# pic18f13k50_3.net
KiCad netlist of a schematic drawn in EAGLE
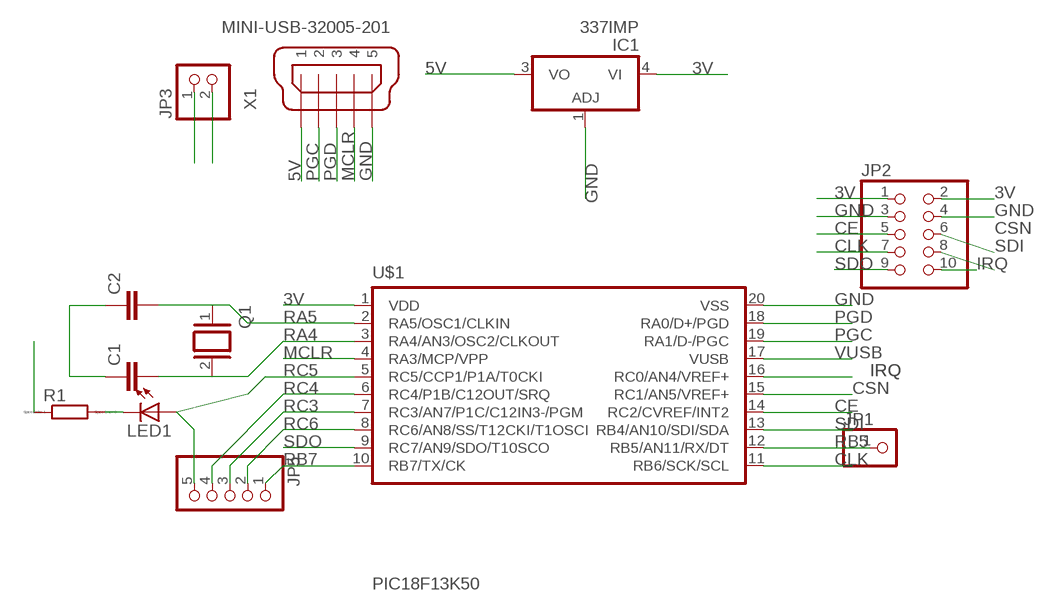
[diagram p0: schematic, sheet 1]

(export (version "E")
  (design (tool "Eeschema 10.0.6"))
  (components
    (comp (ref "C1")
      (value "C-EUC0805")
      (footprint "eagle-import:C0805")
      (libsource (lib "eagle-import") (part "C-EUC0805"))
    )
    (comp (ref "C2")
      (value "C-EUC0805")
      (footprint "eagle-import:C0805")
      (libsource (lib "eagle-import") (part "C-EUC0805"))
    )
    (comp (ref "IC1")
      (value "337IMP")
      (footprint "eagle-import:SOT223")
      (libsource (lib "eagle-import") (part "337IMP"))
    )
    (comp (ref "JP1")
      (value "PINHD-1X1")
      (footprint "eagle-import:1X01")
      (libsource (lib "eagle-import") (part "PINHD-1X1"))
    )
    (comp (ref "JP2")
      (value "PINHD-2X5")
      (footprint "eagle-import:2X05")
      (libsource (lib "eagle-import") (part "PINHD-2X5"))
    )
    (comp (ref "JP3")
      (value "PINHD-1X2")
      (footprint "eagle-import:1X02")
      (libsource (lib "eagle-import") (part "PINHD-1X2"))
    )
    (comp (ref "JP5")
      (value "PINHD-1X5")
      (footprint "eagle-import:1X05")
      (libsource (lib "eagle-import") (part "PINHD-1X5"))
    )
    (comp (ref "LED1")
      (value "LEDCHIP-LED0805")
      (footprint "eagle-import:CHIP-LED0805")
      (libsource (lib "eagle-import") (part "LEDCHIP-LED0805"))
    )
    (comp (ref "Q1")
      (value "XTAL/S")
      (footprint "eagle-import:QS")
      (libsource (lib "eagle-import") (part "XTAL/S"))
    )
    (comp (ref "R1") (value "R") (footprint "eagle-import:R0805") (libsource (lib "eagle-import") (part "R")))
    (comp (ref "U$1")
      (value "PIC18F13K50")
      (footprint "eagle-import:SSOP20")
      (libsource (lib "eagle-import") (part "PIC18F13K50"))
    )
    (comp (ref "X1")
      (value "MINI-USB-32005-201")
      (footprint "eagle-import:32005-201")
      (libsource (lib "eagle-import") (part "MINI-USB-32005-201"))
    )
  )
  (nets
    (net (code "1") (name "/3V") (class "Default")
      (node (ref "IC1") (pin "4") (pinfunction "VI_4") (pintype "input"))
      (node (ref "JP2") (pin "1") (pinfunction "1_1") (pintype "passive"))
      (node (ref "JP2") (pin "2") (pinfunction "2_2") (pintype "passive"))
      (node (ref "JP3") (pin "1") (pinfunction "1_1") (pintype "passive"))
      (node (ref "R1") (pin "1") (pinfunction "1_1") (pintype "passive"))
      (node (ref "U$1") (pin "1") (pinfunction "VDD_1") (pintype "power_in"))
    )
    (net (code "2") (name "/5V") (class "Default")
      (node (ref "IC1") (pin "3") (pinfunction "VO_3") (pintype "passive"))
      (node (ref "JP3") (pin "2") (pinfunction "2_2") (pintype "passive"))
      (node (ref "X1") (pin "1") (pinfunction "1_1") (pintype "passive"))
    )
    (net (code "3") (name "/CE") (class "Default")
      (node (ref "JP2") (pin "5") (pinfunction "5_5") (pintype "passive"))
      (node (ref "U$1") (pin "14") (pinfunction "RC2/CVREF/INT2_14") (pintype "bidirectional"))
    )
    (net (code "4") (name "/CLK") (class "Default")
      (node (ref "JP2") (pin "7") (pinfunction "7_7") (pintype "passive"))
      (node (ref "U$1") (pin "11") (pinfunction "RB6/SCK/SCL_11") (pintype "bidirectional"))
    )
    (net (code "5") (name "/CSN") (class "Default")
      (node (ref "JP2") (pin "6") (pinfunction "6_6") (pintype "passive"))
      (node (ref "U$1") (pin "15") (pinfunction "RC1/AN5/VREF+_15") (pintype "bidirectional"))
    )
    (net (code "6") (name "/GND") (class "Default")
      (node (ref "C1") (pin "1") (pinfunction "1_1") (pintype "passive"))
      (node (ref "C2") (pin "1") (pinfunction "1_1") (pintype "passive"))
      (node (ref "IC1") (pin "1") (pinfunction "ADJ_1") (pintype "input"))
      (node (ref "JP2") (pin "3") (pinfunction "3_3") (pintype "passive"))
      (node (ref "JP2") (pin "4") (pinfunction "4_4") (pintype "passive"))
      (node (ref "U$1") (pin "20") (pinfunction "VSS_20") (pintype "power_in"))
      (node (ref "X1") (pin "5") (pinfunction "5_5") (pintype "passive"))
    )
    (net (code "7") (name "/IRQ") (class "Default")
      (node (ref "JP2") (pin "10") (pinfunction "10_10") (pintype "passive"))
      (node (ref "U$1") (pin "16") (pinfunction "RC0/AN4/VREF+_16") (pintype "bidirectional"))
    )
    (net (code "8") (name "/MCLR") (class "Default")
      (node (ref "U$1") (pin "4") (pinfunction "RA3/MCP/VPP_4") (pintype "bidirectional"))
      (node (ref "X1") (pin "4") (pinfunction "4_4") (pintype "passive"))
    )
    (net (code "9") (name "/PGC") (class "Default")
      (node (ref "U$1") (pin "19") (pinfunction "RA1/D-/PGC_19") (pintype "bidirectional"))
      (node (ref "X1") (pin "2") (pinfunction "2_2") (pintype "passive"))
    )
    (net (code "10") (name "/PGD") (class "Default")
      (node (ref "U$1") (pin "18") (pinfunction "RA0/D+/PGD_18") (pintype "bidirectional"))
      (node (ref "X1") (pin "3") (pinfunction "3_3") (pintype "passive"))
    )
    (net (code "11") (name "/RA4") (class "Default")
      (node (ref "C1") (pin "2") (pinfunction "2_2") (pintype "passive"))
      (node (ref "Q1") (pin "2") (pinfunction "2_2") (pintype "passive"))
      (node (ref "U$1") (pin "3") (pinfunction "RA4/AN3/OSC2/CLKOUT_3") (pintype "input"))
    )
    (net (code "12") (name "/RA5") (class "Default")
      (node (ref "C2") (pin "2") (pinfunction "2_2") (pintype "passive"))
      (node (ref "Q1") (pin "1") (pinfunction "1_1") (pintype "passive"))
      (node (ref "U$1") (pin "2") (pinfunction "RA5/OSC1/CLKIN_2") (pintype "power_in"))
    )
    (net (code "13") (name "/RB5") (class "Default")
      (node (ref "JP1") (pin "1") (pinfunction "1_1") (pintype "passive"))
      (node (ref "U$1") (pin "12") (pinfunction "RB5/AN11/RX/DT_12") (pintype "bidirectional"))
    )
    (net (code "14") (name "/RB7") (class "Default")
      (node (ref "JP5") (pin "1") (pinfunction "1_1") (pintype "passive"))
      (node (ref "U$1") (pin "10") (pinfunction "RB7/TX/CK_10") (pintype "power_in"))
    )
    (net (code "15") (name "/RC3") (class "Default")
      (node (ref "JP5") (pin "3") (pinfunction "3_3") (pintype "passive"))
      (node (ref "U$1") (pin "7") (pinfunction "RC3/AN7/P1C/C12IN3-/PGM_7") (pintype "bidirectional"))
    )
    (net (code "16") (name "/RC4") (class "Default")
      (node (ref "JP5") (pin "4") (pinfunction "4_4") (pintype "passive"))
      (node (ref "U$1") (pin "6") (pinfunction "RC4/P1B/C12OUT/SRQ_6") (pintype "bidirectional"))
    )
    (net (code "17") (name "/RC5") (class "Default")
      (node (ref "JP5") (pin "5") (pinfunction "5_5") (pintype "passive"))
      (node (ref "LED1") (pin "A") (pinfunction "A_A") (pintype "passive"))
      (node (ref "U$1") (pin "5") (pinfunction "RC5/CCP1/P1A/T0CKI_5") (pintype "bidirectional"))
    )
    (net (code "18") (name "/RC6") (class "Default")
      (node (ref "JP5") (pin "2") (pinfunction "2_2") (pintype "passive"))
      (node (ref "U$1") (pin "8") (pinfunction "RC6/AN8/SS/T12CKI/T1OSCI_8") (pintype "bidirectional"))
    )
    (net (code "19") (name "/SDI") (class "Default")
      (node (ref "JP2") (pin "8") (pinfunction "8_8") (pintype "passive"))
      (node (ref "U$1") (pin "13") (pinfunction "RB4/AN10/SDI/SDA_13") (pintype "bidirectional"))
    )
    (net (code "20") (name "/SDO") (class "Default")
      (node (ref "JP2") (pin "9") (pinfunction "9_9") (pintype "passive"))
      (node (ref "U$1") (pin "9") (pinfunction "RC7/AN9/SDO/T10SCO_9") (pintype "bidirectional"))
    )
    (net (code "21") (name "/VUSB") (class "Default")
      (node (ref "U$1") (pin "17") (pinfunction "VUSB_17") (pintype "bidirectional"))
    )
    (net (code "22") (name "Net-(LED1-PadC)") (class "Default")
      (node (ref "LED1") (pin "C") (pinfunction "C_C") (pintype "passive"))
      (node (ref "R1") (pin "2") (pinfunction "2_2") (pintype "passive"))
    )
  )
)
